# PWR_MGMT.net
KiCad netlist of a schematic drawn in Altium Designer
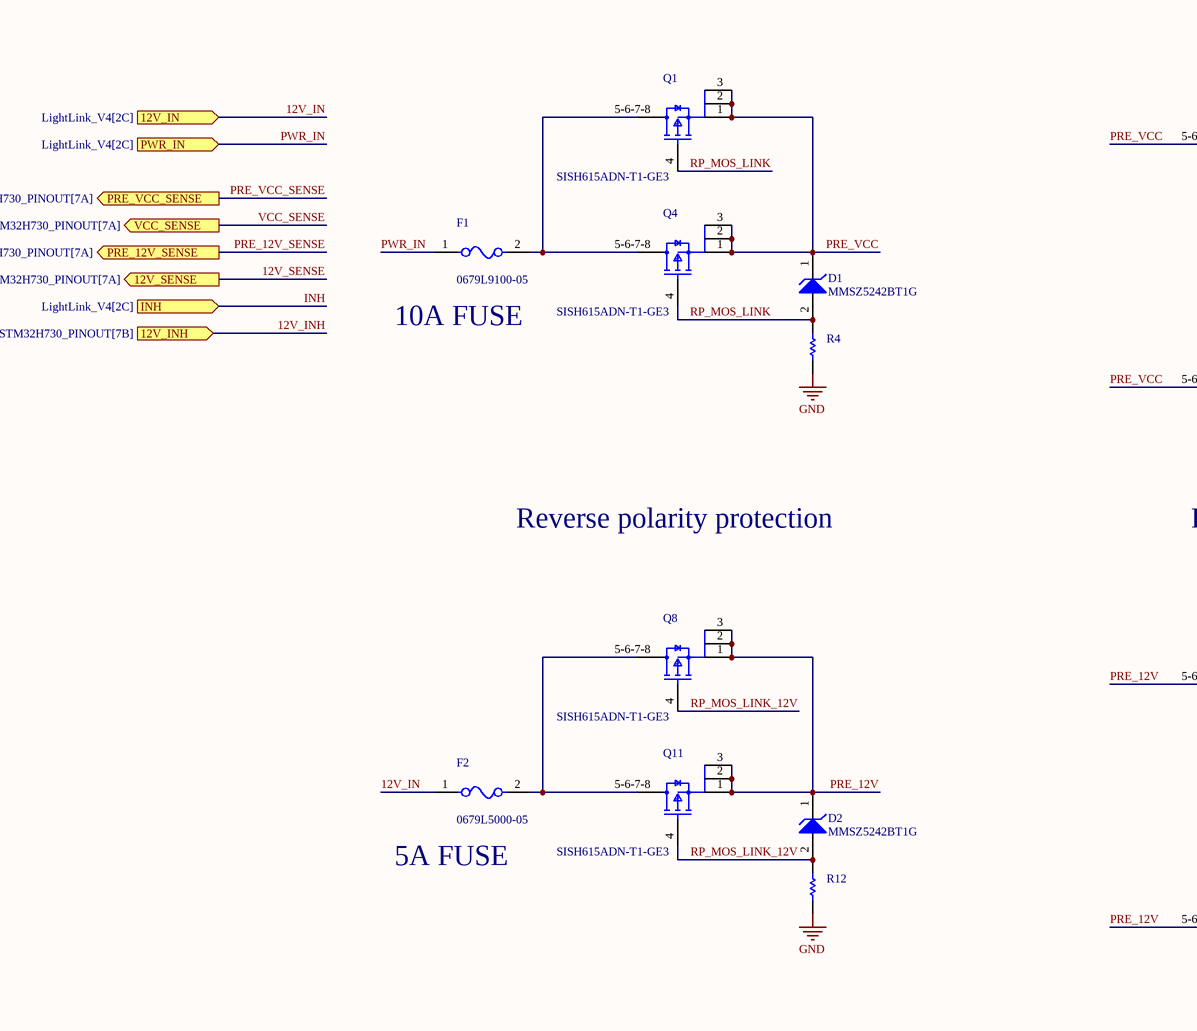
[diagram p0: PWR_MGMT.SchDoc, left]
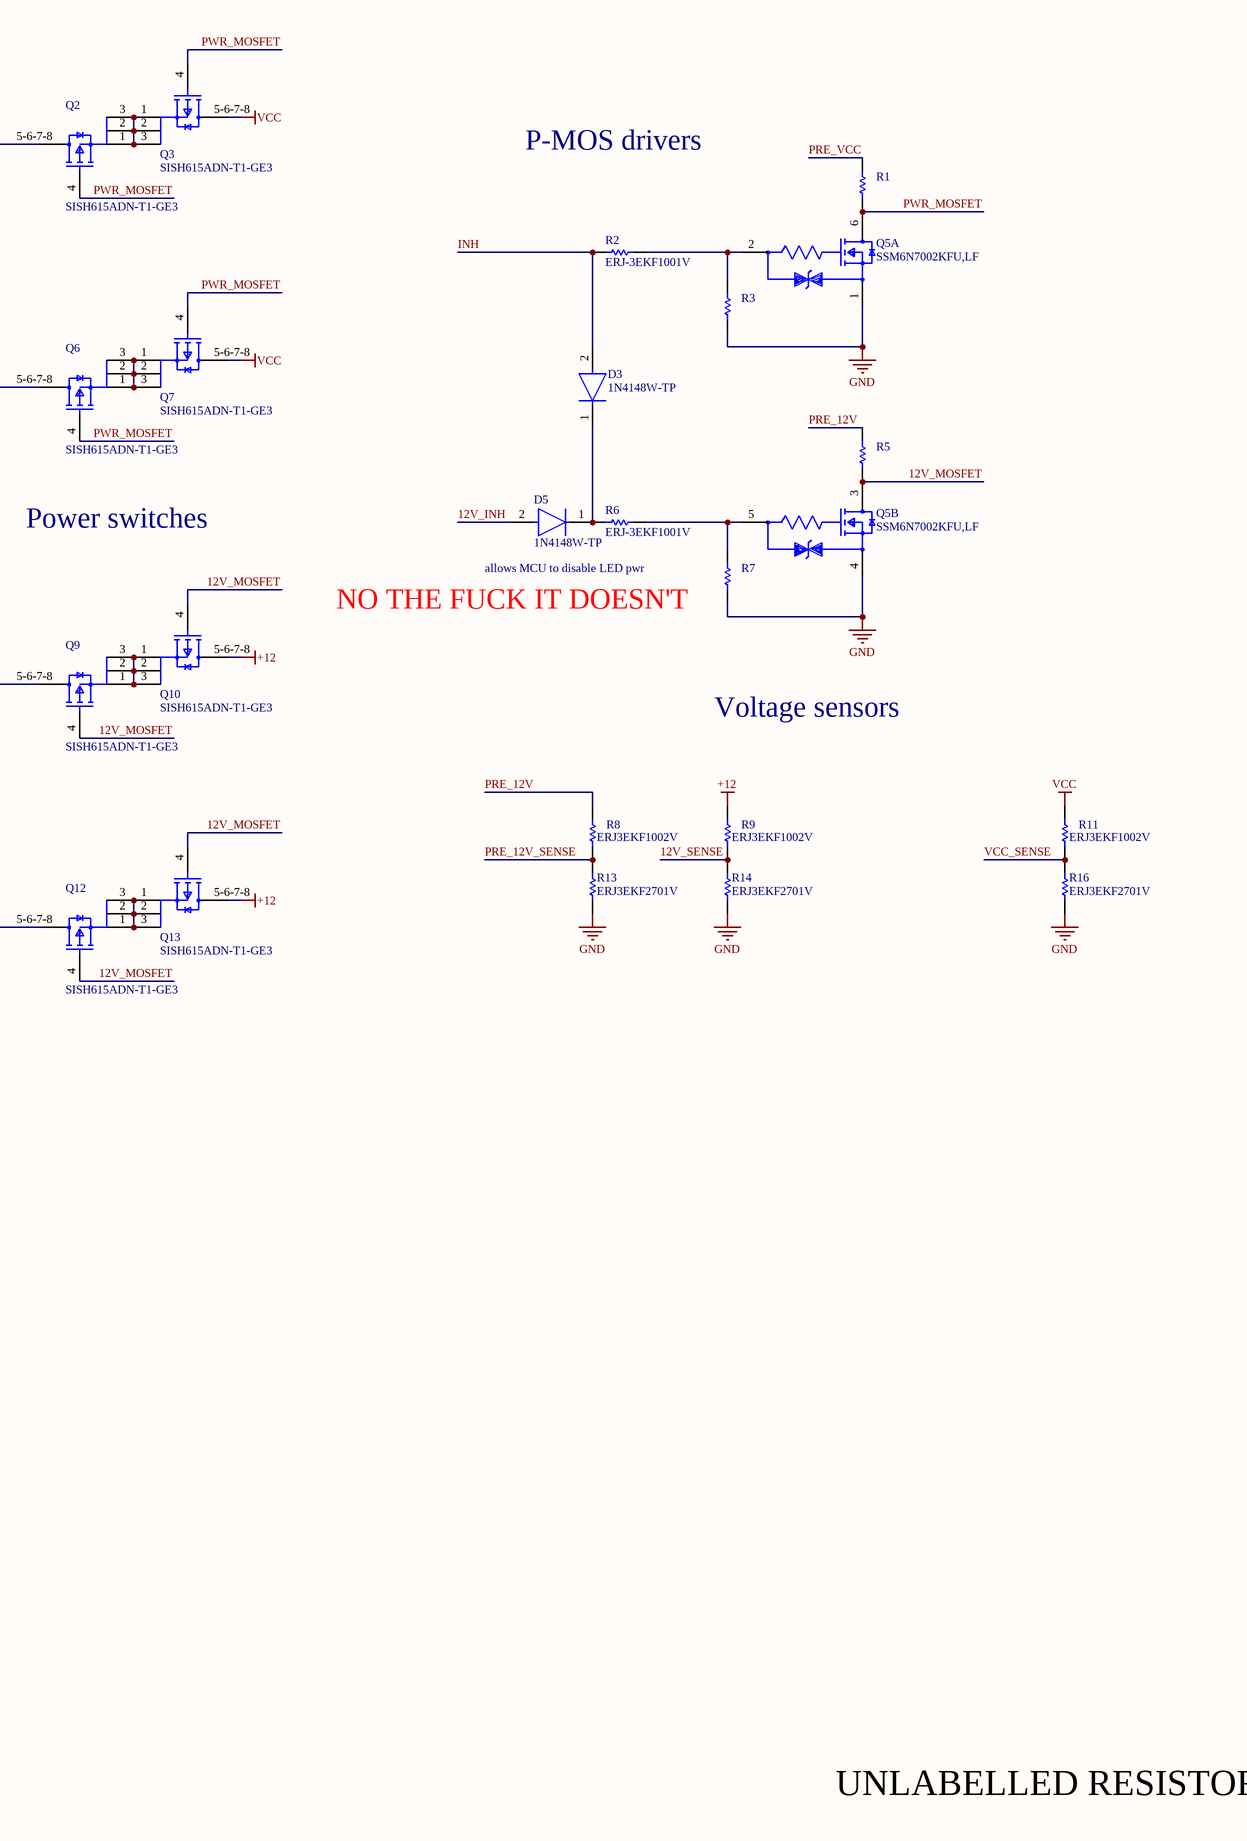
[diagram p1: PWR_MGMT.SchDoc, right]

(export (version "E")
  (design (tool "Eeschema 10.0.6"))
  (components
    (comp (ref "D1")
      (value "MMSZ5242BT1G")
      (footprint "ONSC-SOD-123-2-425-04_V")
      (description "Zener Voltage Regulator, 500 mW, 2-Pin SOD-123, Pb-Free, Tape and Reel")
      (fields (field (name "MANUFACTURER") "On Semiconductor"))
      (libsource (lib "Altium Content Vault") (part "ONSC-K1A2-2"))
    )
    (comp (ref "D2")
      (value "MMSZ5242BT1G")
      (footprint "ONSC-SOD-123-2-425-04_V")
      (description "Zener Voltage Regulator, 500 mW, 2-Pin SOD-123, Pb-Free, Tape and Reel")
      (fields (field (name "MANUFACTURER") "On Semiconductor"))
      (libsource (lib "Altium Content Vault") (part "ONSC-K1A2-2"))
    )
    (comp (ref "D3")
      (value "1N4148W-TP")
      (footprint "FP-SOD-123-IPC_A")
      (description "DIODE GEN PURP 100V 150MA SOD123")
      (libsource (lib "Altium Content Vault") (part "d7152d700b627762746794eb795d46e"))
    )
    (comp (ref "D5")
      (value "1N4148W-TP")
      (footprint "FP-SOD-123-IPC_A")
      (description "DIODE GEN PURP 100V 150MA SOD123")
      (libsource (lib "Altium Content Vault") (part "d7152d700b627762746794eb795d46e"))
    )
    (comp (ref "F1")
      (value "0679L9100-05")
      (footprint "FP-0679L-MFG")
      (description "DIFF P#!!!\r\n\r\nFUSE BRD MNT 10A 125VAC/VDC")
      (fields
        (field (name "OCTOPART") "https://octopart.com/0679l9150-01-bel+fuse-70850665")
        (field (name "MANUFACTURER") "Bel Fuse")
      )
      (libsource (lib "Altium Content Vault") (part "5bcf9b9f640e542cf0359d10258e979"))
    )
    (comp (ref "F2")
      (value "0679L5000-05")
      (footprint "FP-0679L-MFG")
      (description "DIFF P#!!!\r\n\r\nFUSE BRD MNT 5A 125VAC/VDC")
      (fields
        (field (name "OCTOPART") "https://octopart.com/0679l9150-01-bel+fuse-70850665")
        (field (name "MANUFACTURER") "Bel Fuse")
      )
      (libsource (lib "Altium Content Vault") (part "5bcf9b9f640e542cf0359d10258e979"))
    )
    (comp (ref "Q1")
      (value "SISH615ADN-T1-GE3")
      (footprint "SISH615ADN-T1-GE3-Footprint-1")
      (description "Trans MOSFET P-CH 20V 22.1A 8-Pin PowerPAK 1212 EP T/R")
      (libsource (lib "uORocketry Hardware") (part "SISH615ADN-T1-GE3-Symbol-1"))
    )
    (comp (ref "Q2")
      (value "SISH615ADN-T1-GE3")
      (footprint "SISH615ADN-T1-GE3-Footprint-1")
      (description "Trans MOSFET P-CH 20V 22.1A 8-Pin PowerPAK 1212 EP T/R")
      (libsource (lib "uORocketry Hardware") (part "SISH615ADN-T1-GE3-Symbol-1"))
    )
    (comp (ref "Q3")
      (value "SISH615ADN-T1-GE3")
      (footprint "SISH615ADN-T1-GE3-Footprint-1")
      (description "Trans MOSFET P-CH 20V 22.1A 8-Pin PowerPAK 1212 EP T/R")
      (libsource (lib "uORocketry Hardware") (part "SISH615ADN-T1-GE3-Symbol-1"))
    )
    (comp (ref "Q4")
      (value "SISH615ADN-T1-GE3")
      (footprint "SISH615ADN-T1-GE3-Footprint-1")
      (description "Trans MOSFET P-CH 20V 22.1A 8-Pin PowerPAK 1212 EP T/R")
      (libsource (lib "uORocketry Hardware") (part "SISH615ADN-T1-GE3-Symbol-1"))
    )
    (comp (ref "Q5")
      (value "SSM6N7002KFU,LF")
      (footprint "FP-SSOP6-P-0_65A-MFG")
      (description "MOSFET 2N-CH 60V 0.3A")
      (libsource (lib "Altium Content Vault") (part "088aa6ac103fdeebe0d1c52ece6b7b9"))
    )
    (comp (ref "Q6")
      (value "SISH615ADN-T1-GE3")
      (footprint "SISH615ADN-T1-GE3-Footprint-1")
      (description "Trans MOSFET P-CH 20V 22.1A 8-Pin PowerPAK 1212 EP T/R")
      (libsource (lib "uORocketry Hardware") (part "SISH615ADN-T1-GE3-Symbol-1"))
    )
    (comp (ref "Q7")
      (value "SISH615ADN-T1-GE3")
      (footprint "SISH615ADN-T1-GE3-Footprint-1")
      (description "Trans MOSFET P-CH 20V 22.1A 8-Pin PowerPAK 1212 EP T/R")
      (libsource (lib "uORocketry Hardware") (part "SISH615ADN-T1-GE3-Symbol-1"))
    )
    (comp (ref "Q8")
      (value "SISH615ADN-T1-GE3")
      (footprint "SISH615ADN-T1-GE3-Footprint-1")
      (description "Trans MOSFET P-CH 20V 22.1A 8-Pin PowerPAK 1212 EP T/R")
      (libsource (lib "uORocketry Hardware") (part "SISH615ADN-T1-GE3-Symbol-1"))
    )
    (comp (ref "Q9")
      (value "SISH615ADN-T1-GE3")
      (footprint "SISH615ADN-T1-GE3-Footprint-1")
      (description "Trans MOSFET P-CH 20V 22.1A 8-Pin PowerPAK 1212 EP T/R")
      (libsource (lib "uORocketry Hardware") (part "SISH615ADN-T1-GE3-Symbol-1"))
    )
    (comp (ref "Q10")
      (value "SISH615ADN-T1-GE3")
      (footprint "SISH615ADN-T1-GE3-Footprint-1")
      (description "Trans MOSFET P-CH 20V 22.1A 8-Pin PowerPAK 1212 EP T/R")
      (libsource (lib "uORocketry Hardware") (part "SISH615ADN-T1-GE3-Symbol-1"))
    )
    (comp (ref "Q11")
      (value "SISH615ADN-T1-GE3")
      (footprint "SISH615ADN-T1-GE3-Footprint-1")
      (description "Trans MOSFET P-CH 20V 22.1A 8-Pin PowerPAK 1212 EP T/R")
      (libsource (lib "uORocketry Hardware") (part "SISH615ADN-T1-GE3-Symbol-1"))
    )
    (comp (ref "Q12")
      (value "SISH615ADN-T1-GE3")
      (footprint "SISH615ADN-T1-GE3-Footprint-1")
      (description "Trans MOSFET P-CH 20V 22.1A 8-Pin PowerPAK 1212 EP T/R")
      (libsource (lib "uORocketry Hardware") (part "SISH615ADN-T1-GE3-Symbol-1"))
    )
    (comp (ref "Q13")
      (value "SISH615ADN-T1-GE3")
      (footprint "SISH615ADN-T1-GE3-Footprint-1")
      (description "Trans MOSFET P-CH 20V 22.1A 8-Pin PowerPAK 1212 EP T/R")
      (libsource (lib "uORocketry Hardware") (part "SISH615ADN-T1-GE3-Symbol-1"))
    )
    (comp (ref "R1")
      (value "ERJ3EKF1002V")
      (footprint "RESC1609X55X30LL15T15")
      (description "Chip Resistor, 10 KOhm, +/- 1%, 0.1 W, -55 to 155 degC, 0603 (1608 Metric), RoHS, Tape and Reel")
      (fields (field (name "TOLERANCE") "1%") (field (name "MANUFACTURER") "Panasonic"))
      (libsource (lib "Altium Content Vault") (part "RES-2"))
    )
    (comp (ref "R2")
      (value "ERJ-3EKF1001V")
      (footprint "RESC1608X55X30LL15T15")
      (fields (field (name "MANUFACTURER") "Panasonic"))
      (libsource (lib "Altium Content Vault") (part "RES"))
    )
    (comp (ref "R3")
      (value "ERJ3EKF1002V")
      (footprint "RESC1609X55X30LL15T15")
      (description "Chip Resistor, 10 KOhm, +/- 1%, 0.1 W, -55 to 155 degC, 0603 (1608 Metric), RoHS, Tape and Reel")
      (fields (field (name "TOLERANCE") "1%") (field (name "MANUFACTURER") "Panasonic"))
      (libsource (lib "Altium Content Vault") (part "RES-2"))
    )
    (comp (ref "R4")
      (value "ERJ3EKF1002V")
      (footprint "RESC1609X55X30LL15T15")
      (description "Chip Resistor, 10 KOhm, +/- 1%, 0.1 W, -55 to 155 degC, 0603 (1608 Metric), RoHS, Tape and Reel")
      (fields (field (name "TOLERANCE") "1%") (field (name "MANUFACTURER") "Panasonic"))
      (libsource (lib "Altium Content Vault") (part "RES-2"))
    )
    (comp (ref "R5")
      (value "ERJ3EKF1002V")
      (footprint "RESC1609X55X30LL15T15")
      (description "Chip Resistor, 10 KOhm, +/- 1%, 0.1 W, -55 to 155 degC, 0603 (1608 Metric), RoHS, Tape and Reel")
      (fields (field (name "TOLERANCE") "1%") (field (name "MANUFACTURER") "Panasonic"))
      (libsource (lib "Altium Content Vault") (part "RES-2"))
    )
    (comp (ref "R6")
      (value "ERJ-3EKF1001V")
      (footprint "RESC1608X55X30LL15T15")
      (fields (field (name "MANUFACTURER") "Panasonic"))
      (libsource (lib "Altium Content Vault") (part "RES"))
    )
    (comp (ref "R7")
      (value "ERJ3EKF1002V")
      (footprint "RESC1609X55X30LL15T15")
      (description "Chip Resistor, 10 KOhm, +/- 1%, 0.1 W, -55 to 155 degC, 0603 (1608 Metric), RoHS, Tape and Reel")
      (fields (field (name "TOLERANCE") "1%") (field (name "MANUFACTURER") "Panasonic"))
      (libsource (lib "Altium Content Vault") (part "RES-2"))
    )
    (comp (ref "R8")
      (value "ERJ3EKF1002V")
      (footprint "RESC1609X55X30LL15T15")
      (description "Chip Resistor, 10 KOhm, +/- 1%, 0.1 W, -55 to 155 degC, 0603 (1608 Metric), RoHS, Tape and Reel")
      (fields (field (name "TOLERANCE") "1%") (field (name "MANUFACTURER") "Panasonic"))
      (libsource (lib "Altium Content Vault") (part "RES-2"))
    )
    (comp (ref "R9")
      (value "ERJ3EKF1002V")
      (footprint "RESC1609X55X30LL15T15")
      (description "Chip Resistor, 10 KOhm, +/- 1%, 0.1 W, -55 to 155 degC, 0603 (1608 Metric), RoHS, Tape and Reel")
      (fields (field (name "TOLERANCE") "1%") (field (name "MANUFACTURER") "Panasonic"))
      (libsource (lib "Altium Content Vault") (part "RES-2"))
    )
    (comp (ref "R11")
      (value "ERJ3EKF1002V")
      (footprint "RESC1609X55X30LL15T15")
      (description "Chip Resistor, 10 KOhm, +/- 1%, 0.1 W, -55 to 155 degC, 0603 (1608 Metric), RoHS, Tape and Reel")
      (fields (field (name "TOLERANCE") "1%") (field (name "MANUFACTURER") "Panasonic"))
      (libsource (lib "Altium Content Vault") (part "RES-2"))
    )
    (comp (ref "R12")
      (value "ERJ3EKF1002V")
      (footprint "RESC1609X55X30LL15T15")
      (description "Chip Resistor, 10 KOhm, +/- 1%, 0.1 W, -55 to 155 degC, 0603 (1608 Metric), RoHS, Tape and Reel")
      (fields (field (name "TOLERANCE") "1%") (field (name "MANUFACTURER") "Panasonic"))
      (libsource (lib "Altium Content Vault") (part "RES-2"))
    )
    (comp (ref "R13")
      (value "ERJ3EKF2701V")
      (footprint "RESC1608X55X30LL15T15")
      (fields (field (name "MANUFACTURER") "Panasonic"))
      (libsource (lib "Altium Content Vault") (part "RES"))
    )
    (comp (ref "R14")
      (value "ERJ3EKF2701V")
      (footprint "RESC1608X55X30LL15T15")
      (fields (field (name "MANUFACTURER") "Panasonic"))
      (libsource (lib "Altium Content Vault") (part "RES"))
    )
    (comp (ref "R16")
      (value "ERJ3EKF2701V")
      (footprint "RESC1608X55X30LL15T15")
      (fields (field (name "MANUFACTURER") "Panasonic"))
      (libsource (lib "Altium Content Vault") (part "RES"))
    )
  )
  (nets
    (net (code "1") (name "+12") (class "Default")
      (node (ref "Q10") (pin "5-6-7-8") (pinfunction "D_5-6-7-8") (pintype "passive"))
      (node (ref "Q13") (pin "5-6-7-8") (pinfunction "D_5-6-7-8") (pintype "passive"))
      (node (ref "R9") (pin "1") (pinfunction "1_1") (pintype "passive"))
    )
    (net (code "2") (name "/12V_IN") (class "Default")
      (node (ref "F2") (pin "1") (pinfunction "1_1") (pintype "passive"))
    )
    (net (code "3") (name "/12V_INH") (class "Default")
      (node (ref "D5") (pin "2") (pinfunction "A_2") (pintype "passive"))
    )
    (net (code "4") (name "/12V_MOSFET") (class "Default")
      (node (ref "Q10") (pin "4") (pinfunction "G_4") (pintype "passive"))
      (node (ref "Q12") (pin "4") (pinfunction "G_4") (pintype "passive"))
      (node (ref "Q13") (pin "4") (pinfunction "G_4") (pintype "passive"))
      (node (ref "Q5") (pin "3") (pinfunction "Drain2_3") (pintype "passive"))
      (node (ref "Q9") (pin "4") (pinfunction "G_4") (pintype "passive"))
      (node (ref "R5") (pin "2") (pinfunction "2_2") (pintype "passive"))
    )
    (net (code "5") (name "/12V_SENSE") (class "Default")
      (node (ref "R14") (pin "2") (pinfunction "2_2") (pintype "passive"))
      (node (ref "R9") (pin "2") (pinfunction "2_2") (pintype "passive"))
    )
    (net (code "6") (name "/INH") (class "Default")
      (node (ref "D3") (pin "2") (pinfunction "A_2") (pintype "passive"))
      (node (ref "R2") (pin "1") (pinfunction "1_1") (pintype "passive"))
    )
    (net (code "7") (name "/PRE_12V") (class "Default")
      (node (ref "D2") (pin "1") (pinfunction "K_1") (pintype "passive"))
      (node (ref "Q11") (pin "1") (pinfunction "S_1") (pintype "passive"))
      (node (ref "Q11") (pin "2") (pinfunction "S_2") (pintype "passive"))
      (node (ref "Q11") (pin "3") (pinfunction "S_3") (pintype "passive"))
      (node (ref "Q12") (pin "5-6-7-8") (pinfunction "D_5-6-7-8") (pintype "passive"))
      (node (ref "Q8") (pin "1") (pinfunction "S_1") (pintype "passive"))
      (node (ref "Q8") (pin "2") (pinfunction "S_2") (pintype "passive"))
      (node (ref "Q8") (pin "3") (pinfunction "S_3") (pintype "passive"))
      (node (ref "Q9") (pin "5-6-7-8") (pinfunction "D_5-6-7-8") (pintype "passive"))
      (node (ref "R5") (pin "1") (pinfunction "1_1") (pintype "passive"))
      (node (ref "R8") (pin "1") (pinfunction "1_1") (pintype "passive"))
    )
    (net (code "8") (name "/PRE_12V_SENSE") (class "Default")
      (node (ref "R13") (pin "2") (pinfunction "2_2") (pintype "passive"))
      (node (ref "R8") (pin "2") (pinfunction "2_2") (pintype "passive"))
    )
    (net (code "9") (name "/PRE_VCC") (class "Default")
      (node (ref "D1") (pin "1") (pinfunction "K_1") (pintype "passive"))
      (node (ref "Q1") (pin "1") (pinfunction "S_1") (pintype "passive"))
      (node (ref "Q1") (pin "2") (pinfunction "S_2") (pintype "passive"))
      (node (ref "Q1") (pin "3") (pinfunction "S_3") (pintype "passive"))
      (node (ref "Q2") (pin "5-6-7-8") (pinfunction "D_5-6-7-8") (pintype "passive"))
      (node (ref "Q4") (pin "1") (pinfunction "S_1") (pintype "passive"))
      (node (ref "Q4") (pin "2") (pinfunction "S_2") (pintype "passive"))
      (node (ref "Q4") (pin "3") (pinfunction "S_3") (pintype "passive"))
      (node (ref "Q6") (pin "5-6-7-8") (pinfunction "D_5-6-7-8") (pintype "passive"))
      (node (ref "R1") (pin "1") (pinfunction "1_1") (pintype "passive"))
    )
    (net (code "11") (name "/PWR_IN") (class "Default")
      (node (ref "F1") (pin "1") (pinfunction "1_1") (pintype "passive"))
    )
    (net (code "12") (name "/PWR_MOSFET") (class "Default")
      (node (ref "Q2") (pin "4") (pinfunction "G_4") (pintype "passive"))
      (node (ref "Q3") (pin "4") (pinfunction "G_4") (pintype "passive"))
      (node (ref "Q5") (pin "6") (pinfunction "Drain1_6") (pintype "passive"))
      (node (ref "Q6") (pin "4") (pinfunction "G_4") (pintype "passive"))
      (node (ref "Q7") (pin "4") (pinfunction "G_4") (pintype "passive"))
      (node (ref "R1") (pin "2") (pinfunction "2_2") (pintype "passive"))
    )
    (net (code "13") (name "/RP_MOS_LINK") (class "Default")
      (node (ref "D1") (pin "2") (pinfunction "A_2") (pintype "passive"))
      (node (ref "Q1") (pin "4") (pinfunction "G_4") (pintype "passive"))
      (node (ref "Q4") (pin "4") (pinfunction "G_4") (pintype "passive"))
      (node (ref "R4") (pin "1") (pinfunction "1_1") (pintype "passive"))
    )
    (net (code "14") (name "/RP_MOS_LINK_12V") (class "Default")
      (node (ref "D2") (pin "2") (pinfunction "A_2") (pintype "passive"))
      (node (ref "Q11") (pin "4") (pinfunction "G_4") (pintype "passive"))
      (node (ref "Q8") (pin "4") (pinfunction "G_4") (pintype "passive"))
      (node (ref "R12") (pin "1") (pinfunction "1_1") (pintype "passive"))
    )
    (net (code "15") (name "/VCC_SENSE") (class "Default")
      (node (ref "R11") (pin "2") (pinfunction "2_2") (pintype "passive"))
      (node (ref "R16") (pin "2") (pinfunction "2_2") (pintype "passive"))
    )
    (net (code "16") (name "GND") (class "Default")
      (node (ref "Q5") (pin "1") (pinfunction "Source1_1") (pintype "passive"))
      (node (ref "Q5") (pin "4") (pinfunction "Source2_4") (pintype "passive"))
      (node (ref "R12") (pin "2") (pinfunction "2_2") (pintype "passive"))
      (node (ref "R13") (pin "1") (pinfunction "1_1") (pintype "passive"))
      (node (ref "R14") (pin "1") (pinfunction "1_1") (pintype "passive"))
      (node (ref "R16") (pin "1") (pinfunction "1_1") (pintype "passive"))
      (node (ref "R3") (pin "2") (pinfunction "2_2") (pintype "passive"))
      (node (ref "R4") (pin "2") (pinfunction "2_2") (pintype "passive"))
      (node (ref "R7") (pin "2") (pinfunction "2_2") (pintype "passive"))
    )
    (net (code "17") (name "Net-(D3-C)") (class "Default")
      (node (ref "D3") (pin "1") (pinfunction "C_1") (pintype "passive"))
      (node (ref "D5") (pin "1") (pinfunction "C_1") (pintype "passive"))
      (node (ref "R6") (pin "1") (pinfunction "1_1") (pintype "passive"))
    )
    (net (code "18") (name "Net-(Q1-D)") (class "Default")
      (node (ref "F1") (pin "2") (pinfunction "2_2") (pintype "passive"))
      (node (ref "Q1") (pin "5-6-7-8") (pinfunction "D_5-6-7-8") (pintype "passive"))
      (node (ref "Q4") (pin "5-6-7-8") (pinfunction "D_5-6-7-8") (pintype "passive"))
    )
    (net (code "19") (name "Net-(Q2-S-Pad1)") (class "Default")
      (node (ref "Q2") (pin "1") (pinfunction "S_1") (pintype "passive"))
      (node (ref "Q2") (pin "2") (pinfunction "S_2") (pintype "passive"))
      (node (ref "Q2") (pin "3") (pinfunction "S_3") (pintype "passive"))
      (node (ref "Q3") (pin "1") (pinfunction "S_1") (pintype "passive"))
      (node (ref "Q3") (pin "2") (pinfunction "S_2") (pintype "passive"))
      (node (ref "Q3") (pin "3") (pinfunction "S_3") (pintype "passive"))
    )
    (net (code "20") (name "Net-(Q5A-Gate1)") (class "Default")
      (node (ref "Q5") (pin "2") (pinfunction "Gate1_2") (pintype "passive"))
      (node (ref "R2") (pin "2") (pinfunction "2_2") (pintype "passive"))
      (node (ref "R3") (pin "1") (pinfunction "1_1") (pintype "passive"))
    )
    (net (code "21") (name "Net-(Q5B-Gate2)") (class "Default")
      (node (ref "Q5") (pin "5") (pinfunction "Gate2_5") (pintype "passive"))
      (node (ref "R6") (pin "2") (pinfunction "2_2") (pintype "passive"))
      (node (ref "R7") (pin "1") (pinfunction "1_1") (pintype "passive"))
    )
    (net (code "22") (name "Net-(Q6-S-Pad1)") (class "Default")
      (node (ref "Q6") (pin "1") (pinfunction "S_1") (pintype "passive"))
      (node (ref "Q6") (pin "2") (pinfunction "S_2") (pintype "passive"))
      (node (ref "Q6") (pin "3") (pinfunction "S_3") (pintype "passive"))
      (node (ref "Q7") (pin "1") (pinfunction "S_1") (pintype "passive"))
      (node (ref "Q7") (pin "2") (pinfunction "S_2") (pintype "passive"))
      (node (ref "Q7") (pin "3") (pinfunction "S_3") (pintype "passive"))
    )
    (net (code "23") (name "Net-(Q10-S-Pad1)") (class "Default")
      (node (ref "Q10") (pin "1") (pinfunction "S_1") (pintype "passive"))
      (node (ref "Q10") (pin "2") (pinfunction "S_2") (pintype "passive"))
      (node (ref "Q10") (pin "3") (pinfunction "S_3") (pintype "passive"))
      (node (ref "Q9") (pin "1") (pinfunction "S_1") (pintype "passive"))
      (node (ref "Q9") (pin "2") (pinfunction "S_2") (pintype "passive"))
      (node (ref "Q9") (pin "3") (pinfunction "S_3") (pintype "passive"))
    )
    (net (code "24") (name "Net-(Q11-D)") (class "Default")
      (node (ref "F2") (pin "2") (pinfunction "2_2") (pintype "passive"))
      (node (ref "Q11") (pin "5-6-7-8") (pinfunction "D_5-6-7-8") (pintype "passive"))
      (node (ref "Q8") (pin "5-6-7-8") (pinfunction "D_5-6-7-8") (pintype "passive"))
    )
    (net (code "25") (name "Net-(Q12-S-Pad1)") (class "Default")
      (node (ref "Q12") (pin "1") (pinfunction "S_1") (pintype "passive"))
      (node (ref "Q12") (pin "2") (pinfunction "S_2") (pintype "passive"))
      (node (ref "Q12") (pin "3") (pinfunction "S_3") (pintype "passive"))
      (node (ref "Q13") (pin "1") (pinfunction "S_1") (pintype "passive"))
      (node (ref "Q13") (pin "2") (pinfunction "S_2") (pintype "passive"))
      (node (ref "Q13") (pin "3") (pinfunction "S_3") (pintype "passive"))
    )
    (net (code "26") (name "VCC") (class "Default")
      (node (ref "Q3") (pin "5-6-7-8") (pinfunction "D_5-6-7-8") (pintype "passive"))
      (node (ref "Q7") (pin "5-6-7-8") (pinfunction "D_5-6-7-8") (pintype "passive"))
      (node (ref "R11") (pin "1") (pinfunction "1_1") (pintype "passive"))
    )
  )
)
